# BeagleBoneBlackRTC.net
KiCad netlist of a schematic drawn in Altium Designer
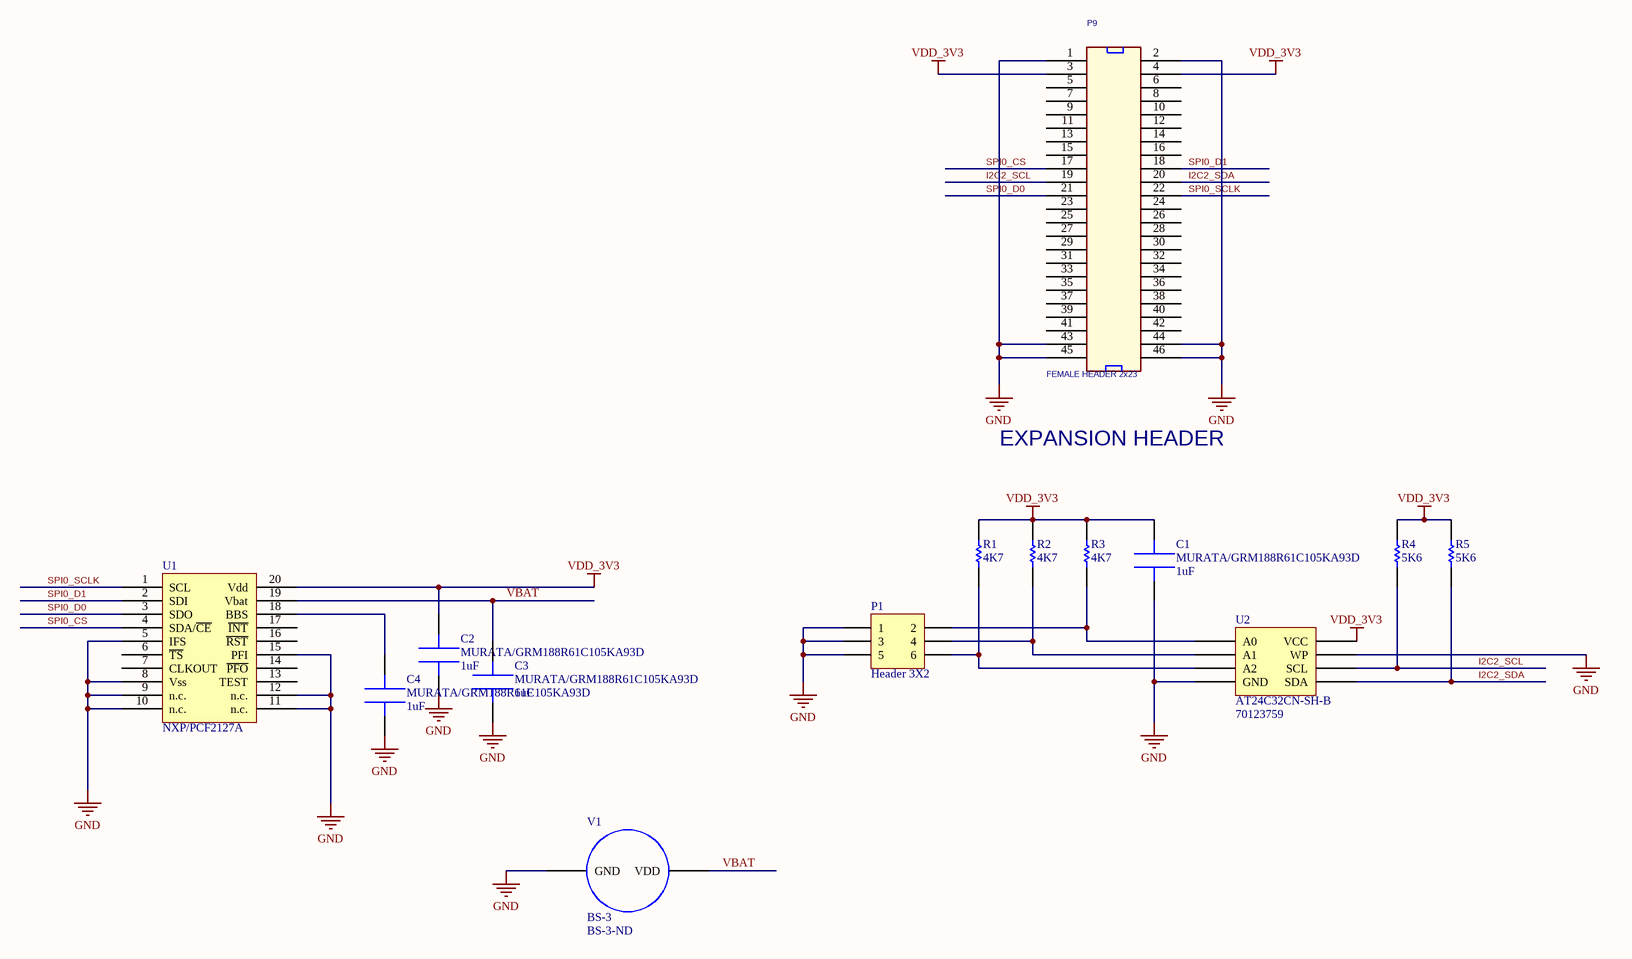
[diagram p0: BeagleBoneBlackRTC.SchDoc]

(export (version "E")
  (design (tool "Eeschema 10.0.6"))
  (components
    (comp (ref "C1")
      (value "MURATA/GRM188R61C105KA93D")
      (footprint "CAPC1608X09N (0603)")
      (description "Capacitor 0603 1uF")
      (fields (field (name "ALTIUM_VALUE") "1uF"))
      (libsource (lib "ece5780") (part "MURATA/GRM188R61C105KA93D"))
    )
    (comp (ref "C2")
      (value "MURATA/GRM188R61C105KA93D")
      (footprint "CAPC1608X09N (0603)")
      (description "Capacitor 0603 1uF")
      (fields (field (name "ALTIUM_VALUE") "1uF"))
      (libsource (lib "ece5780") (part "MURATA/GRM188R61C105KA93D"))
    )
    (comp (ref "C3")
      (value "MURATA/GRM188R61C105KA93D")
      (footprint "CAPC1608X09N (0603)")
      (description "Capacitor 0603 1uF")
      (fields (field (name "ALTIUM_VALUE") "1uF"))
      (libsource (lib "ece5780") (part "MURATA/GRM188R61C105KA93D"))
    )
    (comp (ref "C4")
      (value "MURATA/GRM188R61C105KA93D")
      (footprint "CAPC1608X09N (0603)")
      (description "Capacitor 0603 1uF")
      (fields (field (name "ALTIUM_VALUE") "1uF"))
      (libsource (lib "ece5780") (part "MURATA/GRM188R61C105KA93D"))
    )
    (comp (ref "P1")
      (value "Header 3X2")
      (footprint "HDR2X3")
      (description "Header, 3-Pin, Dual row")
      (fields (field (name "PUBLISHER") "Altium Limited"))
      (libsource (lib "Miscellaneous Connectors") (part "Header 3X2"))
    )
    (comp (ref "P9")
      (value "FEMALE HEADER 2x23")
      (description "CONN HEADER FMAL 46PS.1\" DL GOLD")
      (fields
        (field (name "MANUFACTURER") "Sullins Connector Solutions")
        (field (name "MANUFACTURER PART NUMBER") "PPPC232LFBN-RC")
      )
      (libsource (lib "BEAGLEBONEBLACK_REV A5B") (part "HDR_46_F_2_0.1_0.1"))
    )
    (comp (ref "R1") (value "4K7") (footprint "RES0603") (libsource (lib "ece5780") (part "4K7")))
    (comp (ref "R2") (value "4K7") (footprint "RES0603") (libsource (lib "ece5780") (part "4K7")))
    (comp (ref "R3") (value "4K7") (footprint "RES0603") (libsource (lib "ece5780") (part "4K7")))
    (comp (ref "R4") (value "5K6") (footprint "RES0603") (libsource (lib "ece5780") (part "5K6")))
    (comp (ref "R5") (value "5K6") (footprint "RES0603") (libsource (lib "ece5780") (part "5K6")))
    (comp (ref "U1")
      (value "NXP/PCF2127A")
      (footprint "NXP/PCF2127A SOT163-1")
      (description "Integrated RTC, TCXO and quartz crystal")
      (libsource (lib "RTC") (part "NXP/PCF2127A"))
    )
    (comp (ref "U2")
      (value "AT24C32CN-SH-B")
      (footprint "SOIC127P600X175-8N")
      (description "SERIAL EEPROM 32K 1.8V,  8 PIN SOIC")
      (fields (field (name "MANUFACTURER") "Atmel") (field (name "SUPPLIER PART NUMBER 1") "70123759"))
      (libsource (lib "EEPROM") (part "AT24C32CN-SH-B"))
    )
    (comp (ref "V1")
      (value "BS-3")
      (footprint "CR2032TH")
      (description "HOLDER COINCELL 2032 RETAINR ARM")
      (fields
        (field (name "MANUFACTURER") "MPD (Memory Protection Devices)")
        (field (name "SUPPLIER PART NUMBER 1") "BS-3-ND")
      )
      (libsource (lib "Misc") (part "BS-3"))
    )
  )
  (nets
    (net (code "1") (name "/I2C2_SCL") (class "Default")
      (node (ref "P9") (pin "19") (pinfunction "10_19") (pintype "passive"))
      (node (ref "R4") (pin "1") (pinfunction "1_1") (pintype "passive"))
      (node (ref "U2") (pin "6") (pinfunction "SCL_6") (pintype "passive"))
    )
    (net (code "2") (name "/I2C2_SDA") (class "Default")
      (node (ref "P9") (pin "20") (pinfunction "35_20") (pintype "passive"))
      (node (ref "R5") (pin "1") (pinfunction "1_1") (pintype "passive"))
      (node (ref "U2") (pin "5") (pinfunction "SDA_5") (pintype "passive"))
    )
    (net (code "3") (name "/SPI0_CS") (class "Default")
      (node (ref "P9") (pin "17") (pinfunction "9_17") (pintype "passive"))
      (node (ref "U1") (pin "4") (pinfunction "SDA/~{CE}_4") (pintype "passive"))
    )
    (net (code "4") (name "/SPI0_D0") (class "Default")
      (node (ref "P9") (pin "21") (pinfunction "11_21") (pintype "passive"))
      (node (ref "U1") (pin "3") (pinfunction "SDO_3") (pintype "passive"))
    )
    (net (code "5") (name "/SPI0_D1") (class "Default")
      (node (ref "P9") (pin "18") (pinfunction "34_18") (pintype "passive"))
      (node (ref "U1") (pin "2") (pinfunction "SDI_2") (pintype "passive"))
    )
    (net (code "6") (name "/SPI0_SCLK") (class "Default")
      (node (ref "P9") (pin "22") (pinfunction "36_22") (pintype "passive"))
      (node (ref "U1") (pin "1") (pinfunction "SCL_1") (pintype "passive"))
    )
    (net (code "7") (name "/VBAT") (class "Default")
      (node (ref "C3") (pin "2") (pinfunction "2_2") (pintype "passive"))
      (node (ref "U1") (pin "19") (pinfunction "Vbat_19") (pintype "passive"))
      (node (ref "V1") (pin "1") (pinfunction "VDD_1") (pintype "passive"))
    )
    (net (code "8") (name "GND") (class "Default")
      (node (ref "C1") (pin "1") (pinfunction "1_1") (pintype "passive"))
      (node (ref "C2") (pin "1") (pinfunction "1_1") (pintype "passive"))
      (node (ref "C3") (pin "1") (pinfunction "1_1") (pintype "passive"))
      (node (ref "C4") (pin "1") (pinfunction "1_1") (pintype "passive"))
      (node (ref "P1") (pin "1") (pinfunction "1_1") (pintype "passive"))
      (node (ref "P1") (pin "3") (pinfunction "3_3") (pintype "passive"))
      (node (ref "P1") (pin "5") (pinfunction "5_5") (pintype "passive"))
      (node (ref "P9") (pin "1") (pinfunction "1_1") (pintype "passive"))
      (node (ref "P9") (pin "2") (pinfunction "26_2") (pintype "passive"))
      (node (ref "P9") (pin "43") (pinfunction "22_43") (pintype "passive"))
      (node (ref "P9") (pin "44") (pinfunction "47_44") (pintype "passive"))
      (node (ref "P9") (pin "45") (pinfunction "23_45") (pintype "passive"))
      (node (ref "P9") (pin "46") (pinfunction "48_46") (pintype "passive"))
      (node (ref "U1") (pin "10") (pinfunction "n.c._10") (pintype "passive"))
      (node (ref "U1") (pin "11") (pinfunction "n.c._11") (pintype "passive"))
      (node (ref "U1") (pin "12") (pinfunction "n.c._12") (pintype "passive"))
      (node (ref "U1") (pin "15") (pinfunction "PFI_15") (pintype "passive"))
      (node (ref "U1") (pin "5") (pinfunction "IFS_5") (pintype "passive"))
      (node (ref "U1") (pin "8") (pinfunction "Vss_8") (pintype "passive"))
      (node (ref "U1") (pin "9") (pinfunction "n.c._9") (pintype "passive"))
      (node (ref "U2") (pin "4") (pinfunction "GND_4") (pintype "passive"))
      (node (ref "U2") (pin "7") (pinfunction "WP_7") (pintype "passive"))
      (node (ref "V1") (pin "0") (pinfunction "GND_0") (pintype "passive"))
    )
    (net (code "9") (name "Net-(U1-BBS)") (class "Default")
      (node (ref "C4") (pin "2") (pinfunction "2_2") (pintype "passive"))
      (node (ref "U1") (pin "18") (pinfunction "BBS_18") (pintype "passive"))
    )
    (net (code "10") (name "Net-(U2-A0)") (class "Default")
      (node (ref "P1") (pin "2") (pinfunction "2_2") (pintype "passive"))
      (node (ref "R3") (pin "1") (pinfunction "1_1") (pintype "passive"))
      (node (ref "U2") (pin "1") (pinfunction "A0_1") (pintype "passive"))
    )
    (net (code "11") (name "Net-(U2-A1)") (class "Default")
      (node (ref "P1") (pin "4") (pinfunction "4_4") (pintype "passive"))
      (node (ref "R2") (pin "1") (pinfunction "1_1") (pintype "passive"))
      (node (ref "U2") (pin "2") (pinfunction "A1_2") (pintype "passive"))
    )
    (net (code "12") (name "Net-(U2-A2)") (class "Default")
      (node (ref "P1") (pin "6") (pinfunction "6_6") (pintype "passive"))
      (node (ref "R1") (pin "1") (pinfunction "1_1") (pintype "passive"))
      (node (ref "U2") (pin "3") (pinfunction "A2_3") (pintype "passive"))
    )
    (net (code "13") (name "VDD_3V3") (class "Default")
      (node (ref "C1") (pin "2") (pinfunction "2_2") (pintype "passive"))
      (node (ref "C2") (pin "2") (pinfunction "2_2") (pintype "passive"))
      (node (ref "P9") (pin "3") (pinfunction "2_3") (pintype "passive"))
      (node (ref "P9") (pin "4") (pinfunction "27_4") (pintype "passive"))
      (node (ref "R1") (pin "2") (pinfunction "2_2") (pintype "passive"))
      (node (ref "R2") (pin "2") (pinfunction "2_2") (pintype "passive"))
      (node (ref "R3") (pin "2") (pinfunction "2_2") (pintype "passive"))
      (node (ref "R4") (pin "2") (pinfunction "2_2") (pintype "passive"))
      (node (ref "R5") (pin "2") (pinfunction "2_2") (pintype "passive"))
      (node (ref "U1") (pin "20") (pinfunction "Vdd_20") (pintype "passive"))
      (node (ref "U2") (pin "8") (pinfunction "VCC_8") (pintype "passive"))
    )
    (net (code "14") (name "unconnected-(P9-3-Pad5)") (class "Default")
      (node (ref "P9") (pin "5") (pinfunction "3_5") (pintype "passive"))
    )
    (net (code "15") (name "unconnected-(P9-4-Pad7)") (class "Default")
      (node (ref "P9") (pin "7") (pinfunction "4_7") (pintype "passive"))
    )
    (net (code "16") (name "unconnected-(P9-5-Pad9)") (class "Default")
      (node (ref "P9") (pin "9") (pinfunction "5_9") (pintype "passive"))
    )
    (net (code "17") (name "unconnected-(P9-6-Pad11)") (class "Default")
      (node (ref "P9") (pin "11") (pinfunction "6_11") (pintype "passive"))
    )
    (net (code "18") (name "unconnected-(P9-7-Pad13)") (class "Default")
      (node (ref "P9") (pin "13") (pinfunction "7_13") (pintype "passive"))
    )
    (net (code "19") (name "unconnected-(P9-8-Pad15)") (class "Default")
      (node (ref "P9") (pin "15") (pinfunction "8_15") (pintype "passive"))
    )
    (net (code "20") (name "unconnected-(P9-12-Pad23)") (class "Default")
      (node (ref "P9") (pin "23") (pinfunction "12_23") (pintype "passive"))
    )
    (net (code "21") (name "unconnected-(P9-13-Pad25)") (class "Default")
      (node (ref "P9") (pin "25") (pinfunction "13_25") (pintype "passive"))
    )
    (net (code "22") (name "unconnected-(P9-14-Pad27)") (class "Default")
      (node (ref "P9") (pin "27") (pinfunction "14_27") (pintype "passive"))
    )
    (net (code "23") (name "unconnected-(P9-15-Pad29)") (class "Default")
      (node (ref "P9") (pin "29") (pinfunction "15_29") (pintype "passive"))
    )
    (net (code "24") (name "unconnected-(P9-16-Pad31)") (class "Default")
      (node (ref "P9") (pin "31") (pinfunction "16_31") (pintype "passive"))
    )
    (net (code "25") (name "unconnected-(P9-17-Pad33)") (class "Default")
      (node (ref "P9") (pin "33") (pinfunction "17_33") (pintype "passive"))
    )
    (net (code "26") (name "unconnected-(P9-18-Pad35)") (class "Default")
      (node (ref "P9") (pin "35") (pinfunction "18_35") (pintype "passive"))
    )
    (net (code "27") (name "unconnected-(P9-19-Pad37)") (class "Default")
      (node (ref "P9") (pin "37") (pinfunction "19_37") (pintype "passive"))
    )
    (net (code "28") (name "unconnected-(P9-20-Pad39)") (class "Default")
      (node (ref "P9") (pin "39") (pinfunction "20_39") (pintype "passive"))
    )
    (net (code "29") (name "unconnected-(P9-21-Pad41)") (class "Default")
      (node (ref "P9") (pin "41") (pinfunction "21_41") (pintype "passive"))
    )
    (net (code "30") (name "unconnected-(P9-28-Pad6)") (class "Default")
      (node (ref "P9") (pin "6") (pinfunction "28_6") (pintype "passive"))
    )
    (net (code "31") (name "unconnected-(P9-29-Pad8)") (class "Default")
      (node (ref "P9") (pin "8") (pinfunction "29_8") (pintype "passive"))
    )
    (net (code "32") (name "unconnected-(P9-30-Pad10)") (class "Default")
      (node (ref "P9") (pin "10") (pinfunction "30_10") (pintype "passive"))
    )
    (net (code "33") (name "unconnected-(P9-31-Pad12)") (class "Default")
      (node (ref "P9") (pin "12") (pinfunction "31_12") (pintype "passive"))
    )
    (net (code "34") (name "unconnected-(P9-32-Pad14)") (class "Default")
      (node (ref "P9") (pin "14") (pinfunction "32_14") (pintype "passive"))
    )
    (net (code "35") (name "unconnected-(P9-33-Pad16)") (class "Default")
      (node (ref "P9") (pin "16") (pinfunction "33_16") (pintype "passive"))
    )
    (net (code "36") (name "unconnected-(P9-37-Pad24)") (class "Default")
      (node (ref "P9") (pin "24") (pinfunction "37_24") (pintype "passive"))
    )
    (net (code "37") (name "unconnected-(P9-38-Pad26)") (class "Default")
      (node (ref "P9") (pin "26") (pinfunction "38_26") (pintype "passive"))
    )
    (net (code "38") (name "unconnected-(P9-39-Pad28)") (class "Default")
      (node (ref "P9") (pin "28") (pinfunction "39_28") (pintype "passive"))
    )
    (net (code "39") (name "unconnected-(P9-40-Pad30)") (class "Default")
      (node (ref "P9") (pin "30") (pinfunction "40_30") (pintype "passive"))
    )
    (net (code "40") (name "unconnected-(P9-41-Pad32)") (class "Default")
      (node (ref "P9") (pin "32") (pinfunction "41_32") (pintype "passive"))
    )
    (net (code "41") (name "unconnected-(P9-42-Pad34)") (class "Default")
      (node (ref "P9") (pin "34") (pinfunction "42_34") (pintype "passive"))
    )
    (net (code "42") (name "unconnected-(P9-43-Pad36)") (class "Default")
      (node (ref "P9") (pin "36") (pinfunction "43_36") (pintype "passive"))
    )
    (net (code "43") (name "unconnected-(P9-44-Pad38)") (class "Default")
      (node (ref "P9") (pin "38") (pinfunction "44_38") (pintype "passive"))
    )
    (net (code "44") (name "unconnected-(P9-45-Pad40)") (class "Default")
      (node (ref "P9") (pin "40") (pinfunction "45_40") (pintype "passive"))
    )
    (net (code "45") (name "unconnected-(P9-46-Pad42)") (class "Default")
      (node (ref "P9") (pin "42") (pinfunction "46_42") (pintype "passive"))
    )
    (net (code "46") (name "unconnected-(U1-CLKOUT-Pad7)") (class "Default")
      (node (ref "U1") (pin "7") (pinfunction "CLKOUT_7") (pintype "passive"))
    )
    (net (code "47") (name "unconnected-(U1-TEST-Pad13)") (class "Default")
      (node (ref "U1") (pin "13") (pinfunction "TEST_13") (pintype "passive"))
    )
    (net (code "48") (name "unconnected-(U1-~{INT}-Pad17)") (class "Default")
      (node (ref "U1") (pin "17") (pinfunction "~{INT}_17") (pintype "passive"))
    )
    (net (code "49") (name "unconnected-(U1-~{PFO}-Pad14)") (class "Default")
      (node (ref "U1") (pin "14") (pinfunction "~{PFO}_14") (pintype "passive"))
    )
    (net (code "50") (name "unconnected-(U1-~{RST}-Pad16)") (class "Default")
      (node (ref "U1") (pin "16") (pinfunction "~{RST}_16") (pintype "passive"))
    )
    (net (code "51") (name "unconnected-(U1-~{TS}-Pad6)") (class "Default")
      (node (ref "U1") (pin "6") (pinfunction "~{TS}_6") (pintype "passive"))
    )
  )
)
